# Supply_System.net
KiCad netlist of a schematic drawn in Altium Designer
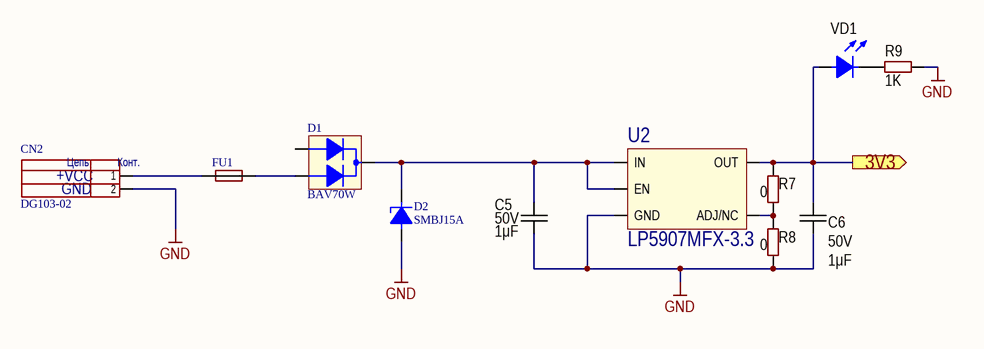
[diagram p0: Supply System.SchDoc]

(export (version "E")
  (design (tool "Eeschema 10.0.6"))
  (components
    (comp (ref "C5")
      (value "1μF")
      (footprint "CAP: 0603")
      (fields
        (field (name "MANUFACTURER") "Yageo")
        (field (name "PARTNUMBER") "CC0603KRX7R7BB104")
        (field (name "VALUEMANUFACTURERPARTNUMBER") "Ceramic capacitor, 1μF, X7R, ±10%, 50V, 0603, -55...+125°C")
        (field (name "VOLTAGE") "50V")
      )
      (libsource (lib "capacitor") (part "Ceramic_0603"))
    )
    (comp (ref "C6")
      (value "1μF")
      (footprint "CAP: 0603")
      (fields
        (field (name "MANUFACTURER") "Yageo")
        (field (name "PARTNUMBER") "CC0603KRX7R7BB104")
        (field (name "VALUEMANUFACTURERPARTNUMBER") "Ceramic capacitor, 1μF, X7R, ±10%, 50V, 0603, -55...+125°C")
        (field (name "VOLTAGE") "50V")
      )
      (libsource (lib "capacitor") (part "Ceramic_0603"))
    )
    (comp (ref "CN2")
      (value "DG103-02")
      (footprint "DG103-02")
      (libsource (lib "connector") (part "DG103-02"))
    )
    (comp (ref "D1") (value "BAV70W") (footprint "SOT323") (libsource (lib "diode") (part "BAV70W")))
    (comp (ref "D2") (value "SMBJ15A") (footprint "DIODE: SMB") (libsource (lib "diode") (part "SMBJ15A")))
    (comp (ref "FU1")
      (value "MF-MSMF020/60-2")
      (footprint "FUSE: 1812")
      (libsource (lib "electromechanics") (part "MF-MSMF020/60-2"))
    )
    (comp (ref "R7")
      (value "0")
      (footprint "RES: 0603")
      (fields
        (field (name "MANUFACTURER") "Yageo")
        (field (name "PARTNUMBER") "RC0603JR-07100RL")
        (field (name "VALUEMANUFACTURERPARTNUMBER") "Resistor film, 0, ±5%, 0603, 0.1W, -55...+125°C")
      )
      (libsource (lib "") (part "Resistor_0603_1"))
    )
    (comp (ref "R8")
      (value "0")
      (footprint "RES: 0603")
      (fields
        (field (name "MANUFACTURER") "Yageo")
        (field (name "PARTNUMBER") "RC0603JR-07100RL")
        (field (name "VALUEMANUFACTURERPARTNUMBER") "Resistor film, 0, ±5%, 0603, 0.1W, -55...+125°C")
      )
      (libsource (lib "") (part "Resistor_0603_1"))
    )
    (comp (ref "R9")
      (value "1K")
      (footprint "RES: 0603")
      (fields
        (field (name "MANUFACTURER") "Yageo")
        (field (name "PARTNUMBER") "RC0603JR-07100RL")
        (field (name "VALUEMANUFACTURERPARTNUMBER") "Resistor film, 1K, ±5%, 0603, 0.1W, -55...+125°C")
      )
      (libsource (lib "resistor") (part "Resistor_0603"))
    )
    (comp (ref "U2")
      (value "LP5907MFX-3.3")
      (footprint "SOT23-5")
      (description "Low drop voltage regulator")
      (libsource (lib "ic-power-supply") (part "LDK320AM120R"))
    )
    (comp (ref "VD1")
      (value "~")
      (footprint "LED: 0603B")
      (fields (field (name "VALUEMANUFACTURERPARTNUMBER") "LED, Green, *, *, *, -55...+150°C"))
      (libsource (lib "diode") (part "LED_single"))
    )
  )
  (nets
    (net (code "1") (name "/3V3") (class "Default")
      (node (ref "C6") (pin "2") (pinfunction "2_2") (pintype "passive"))
      (node (ref "R7") (pin "2") (pinfunction "2_2") (pintype "passive"))
      (node (ref "U2") (pin "5") (pinfunction "OUT_5") (pintype "passive"))
      (node (ref "VD1") (pin "1") (pinfunction "A_1") (pintype "passive"))
    )
    (net (code "2") (name "GND") (class "Default")
      (node (ref "C5") (pin "1") (pinfunction "1_1") (pintype "passive"))
      (node (ref "C6") (pin "1") (pinfunction "1_1") (pintype "passive"))
      (node (ref "CN2") (pin "2") (pinfunction "2_2") (pintype "passive"))
      (node (ref "D2") (pin "1") (pinfunction "1_1") (pintype "passive"))
      (node (ref "R8") (pin "1") (pinfunction "1_1") (pintype "passive"))
      (node (ref "R9") (pin "1") (pinfunction "1_1") (pintype "passive"))
      (node (ref "U2") (pin "2") (pinfunction "GND_2") (pintype "passive"))
    )
    (net (code "3") (name "Net-(CN2-Pad1)") (class "Default")
      (node (ref "CN2") (pin "1") (pinfunction "1_1") (pintype "passive"))
      (node (ref "FU1") (pin "1") (pinfunction "1_1") (pintype "passive"))
    )
    (net (code "4") (name "Net-(D1-Pad2)") (class "Default")
      (node (ref "D1") (pin "2") (pinfunction "2_2") (pintype "passive"))
      (node (ref "FU1") (pin "2") (pinfunction "2_2") (pintype "passive"))
    )
    (net (code "5") (name "Net-(U2-ADJ{slash}NC)") (class "Default")
      (node (ref "R7") (pin "1") (pinfunction "1_1") (pintype "passive"))
      (node (ref "R8") (pin "2") (pinfunction "2_2") (pintype "passive"))
      (node (ref "U2") (pin "4") (pinfunction "ADJ/NC_4") (pintype "passive"))
    )
    (net (code "6") (name "Net-(U2-EN)") (class "Default")
      (node (ref "C5") (pin "2") (pinfunction "2_2") (pintype "passive"))
      (node (ref "D1") (pin "3") (pinfunction "3_3") (pintype "passive"))
      (node (ref "D2") (pin "2") (pinfunction "2_2") (pintype "passive"))
      (node (ref "U2") (pin "1") (pinfunction "IN_1") (pintype "passive"))
      (node (ref "U2") (pin "3") (pinfunction "EN_3") (pintype "passive"))
    )
    (net (code "7") (name "Net-(VD1-C)") (class "Default")
      (node (ref "R9") (pin "2") (pinfunction "2_2") (pintype "passive"))
      (node (ref "VD1") (pin "2") (pinfunction "C_2") (pintype "passive"))
    )
    (net (code "8") (name "unconnected-(D1-Pad1)") (class "Default")
      (node (ref "D1") (pin "1") (pinfunction "1_1") (pintype "passive"))
    )
  )
)
